# test.net
KiCad netlist of a schematic drawn in EAGLE
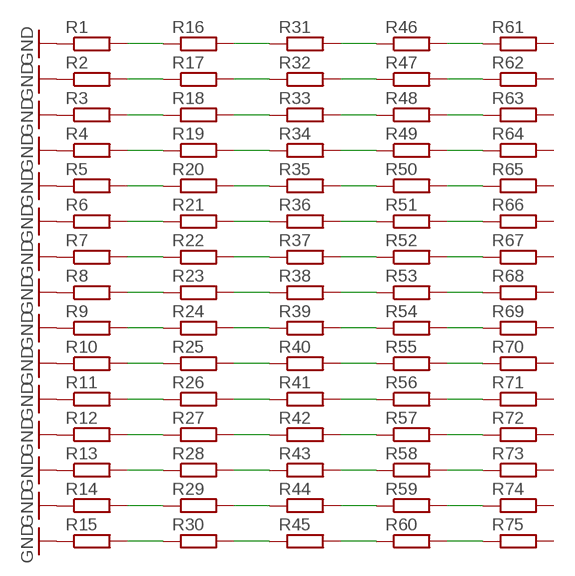
[diagram p0: schematic, sheet 1]

(export (version "E")
  (design (tool "Eeschema 10.0.6"))
  (components
    (comp (ref "R1")
      (value "R-EU_R1206")
      (footprint "eagle-import:R1206")
      (libsource (lib "eagle-import") (part "R-EU_R1206"))
    )
    (comp (ref "R2")
      (value "R-EU_R1206")
      (footprint "eagle-import:R1206")
      (libsource (lib "eagle-import") (part "R-EU_R1206"))
    )
    (comp (ref "R3")
      (value "R-EU_R1206")
      (footprint "eagle-import:R1206")
      (libsource (lib "eagle-import") (part "R-EU_R1206"))
    )
    (comp (ref "R4")
      (value "R-EU_R1206")
      (footprint "eagle-import:R1206")
      (libsource (lib "eagle-import") (part "R-EU_R1206"))
    )
    (comp (ref "R5")
      (value "R-EU_R1206")
      (footprint "eagle-import:R1206")
      (libsource (lib "eagle-import") (part "R-EU_R1206"))
    )
    (comp (ref "R6")
      (value "R-EU_R1206")
      (footprint "eagle-import:R1206")
      (libsource (lib "eagle-import") (part "R-EU_R1206"))
    )
    (comp (ref "R7")
      (value "R-EU_R1206")
      (footprint "eagle-import:R1206")
      (libsource (lib "eagle-import") (part "R-EU_R1206"))
    )
    (comp (ref "R8")
      (value "R-EU_R1206")
      (footprint "eagle-import:R1206")
      (libsource (lib "eagle-import") (part "R-EU_R1206"))
    )
    (comp (ref "R9")
      (value "R-EU_R1206")
      (footprint "eagle-import:R1206")
      (libsource (lib "eagle-import") (part "R-EU_R1206"))
    )
    (comp (ref "R10")
      (value "R-EU_R1206")
      (footprint "eagle-import:R1206")
      (libsource (lib "eagle-import") (part "R-EU_R1206"))
    )
    (comp (ref "R11")
      (value "R-EU_R1206")
      (footprint "eagle-import:R1206")
      (libsource (lib "eagle-import") (part "R-EU_R1206"))
    )
    (comp (ref "R12")
      (value "R-EU_R1206")
      (footprint "eagle-import:R1206")
      (libsource (lib "eagle-import") (part "R-EU_R1206"))
    )
    (comp (ref "R13")
      (value "R-EU_R1206")
      (footprint "eagle-import:R1206")
      (libsource (lib "eagle-import") (part "R-EU_R1206"))
    )
    (comp (ref "R14")
      (value "R-EU_R1206")
      (footprint "eagle-import:R1206")
      (libsource (lib "eagle-import") (part "R-EU_R1206"))
    )
    (comp (ref "R15")
      (value "R-EU_R1206")
      (footprint "eagle-import:R1206")
      (libsource (lib "eagle-import") (part "R-EU_R1206"))
    )
    (comp (ref "R16")
      (value "R-EU_R1206")
      (footprint "eagle-import:R1206")
      (libsource (lib "eagle-import") (part "R-EU_R1206"))
    )
    (comp (ref "R17")
      (value "R-EU_R1206")
      (footprint "eagle-import:R1206")
      (libsource (lib "eagle-import") (part "R-EU_R1206"))
    )
    (comp (ref "R18")
      (value "R-EU_R1206")
      (footprint "eagle-import:R1206")
      (libsource (lib "eagle-import") (part "R-EU_R1206"))
    )
    (comp (ref "R19")
      (value "R-EU_R1206")
      (footprint "eagle-import:R1206")
      (libsource (lib "eagle-import") (part "R-EU_R1206"))
    )
    (comp (ref "R20")
      (value "R-EU_R1206")
      (footprint "eagle-import:R1206")
      (libsource (lib "eagle-import") (part "R-EU_R1206"))
    )
    (comp (ref "R21")
      (value "R-EU_R1206")
      (footprint "eagle-import:R1206")
      (libsource (lib "eagle-import") (part "R-EU_R1206"))
    )
    (comp (ref "R22")
      (value "R-EU_R1206")
      (footprint "eagle-import:R1206")
      (libsource (lib "eagle-import") (part "R-EU_R1206"))
    )
    (comp (ref "R23")
      (value "R-EU_R1206")
      (footprint "eagle-import:R1206")
      (libsource (lib "eagle-import") (part "R-EU_R1206"))
    )
    (comp (ref "R24")
      (value "R-EU_R1206")
      (footprint "eagle-import:R1206")
      (libsource (lib "eagle-import") (part "R-EU_R1206"))
    )
    (comp (ref "R25")
      (value "R-EU_R1206")
      (footprint "eagle-import:R1206")
      (libsource (lib "eagle-import") (part "R-EU_R1206"))
    )
    (comp (ref "R26")
      (value "R-EU_R1206")
      (footprint "eagle-import:R1206")
      (libsource (lib "eagle-import") (part "R-EU_R1206"))
    )
    (comp (ref "R27")
      (value "R-EU_R1206")
      (footprint "eagle-import:R1206")
      (libsource (lib "eagle-import") (part "R-EU_R1206"))
    )
    (comp (ref "R28")
      (value "R-EU_R1206")
      (footprint "eagle-import:R1206")
      (libsource (lib "eagle-import") (part "R-EU_R1206"))
    )
    (comp (ref "R29")
      (value "R-EU_R1206")
      (footprint "eagle-import:R1206")
      (libsource (lib "eagle-import") (part "R-EU_R1206"))
    )
    (comp (ref "R30")
      (value "R-EU_R1206")
      (footprint "eagle-import:R1206")
      (libsource (lib "eagle-import") (part "R-EU_R1206"))
    )
    (comp (ref "R31")
      (value "R-EU_R1206")
      (footprint "eagle-import:R1206")
      (libsource (lib "eagle-import") (part "R-EU_R1206"))
    )
    (comp (ref "R32")
      (value "R-EU_R1206")
      (footprint "eagle-import:R1206")
      (libsource (lib "eagle-import") (part "R-EU_R1206"))
    )
    (comp (ref "R33")
      (value "R-EU_R1206")
      (footprint "eagle-import:R1206")
      (libsource (lib "eagle-import") (part "R-EU_R1206"))
    )
    (comp (ref "R34")
      (value "R-EU_R1206")
      (footprint "eagle-import:R1206")
      (libsource (lib "eagle-import") (part "R-EU_R1206"))
    )
    (comp (ref "R35")
      (value "R-EU_R1206")
      (footprint "eagle-import:R1206")
      (libsource (lib "eagle-import") (part "R-EU_R1206"))
    )
    (comp (ref "R36")
      (value "R-EU_R1206")
      (footprint "eagle-import:R1206")
      (libsource (lib "eagle-import") (part "R-EU_R1206"))
    )
    (comp (ref "R37")
      (value "R-EU_R1206")
      (footprint "eagle-import:R1206")
      (libsource (lib "eagle-import") (part "R-EU_R1206"))
    )
    (comp (ref "R38")
      (value "R-EU_R1206")
      (footprint "eagle-import:R1206")
      (libsource (lib "eagle-import") (part "R-EU_R1206"))
    )
    (comp (ref "R39")
      (value "R-EU_R1206")
      (footprint "eagle-import:R1206")
      (libsource (lib "eagle-import") (part "R-EU_R1206"))
    )
    (comp (ref "R40")
      (value "R-EU_R1206")
      (footprint "eagle-import:R1206")
      (libsource (lib "eagle-import") (part "R-EU_R1206"))
    )
    (comp (ref "R41")
      (value "R-EU_R1206")
      (footprint "eagle-import:R1206")
      (libsource (lib "eagle-import") (part "R-EU_R1206"))
    )
    (comp (ref "R42")
      (value "R-EU_R1206")
      (footprint "eagle-import:R1206")
      (libsource (lib "eagle-import") (part "R-EU_R1206"))
    )
    (comp (ref "R43")
      (value "R-EU_R1206")
      (footprint "eagle-import:R1206")
      (libsource (lib "eagle-import") (part "R-EU_R1206"))
    )
    (comp (ref "R44")
      (value "R-EU_R1206")
      (footprint "eagle-import:R1206")
      (libsource (lib "eagle-import") (part "R-EU_R1206"))
    )
    (comp (ref "R45")
      (value "R-EU_R1206")
      (footprint "eagle-import:R1206")
      (libsource (lib "eagle-import") (part "R-EU_R1206"))
    )
    (comp (ref "R46")
      (value "R-EU_R1206")
      (footprint "eagle-import:R1206")
      (libsource (lib "eagle-import") (part "R-EU_R1206"))
    )
    (comp (ref "R47")
      (value "R-EU_R1206")
      (footprint "eagle-import:R1206")
      (libsource (lib "eagle-import") (part "R-EU_R1206"))
    )
    (comp (ref "R48")
      (value "R-EU_R1206")
      (footprint "eagle-import:R1206")
      (libsource (lib "eagle-import") (part "R-EU_R1206"))
    )
    (comp (ref "R49")
      (value "R-EU_R1206")
      (footprint "eagle-import:R1206")
      (libsource (lib "eagle-import") (part "R-EU_R1206"))
    )
    (comp (ref "R50")
      (value "R-EU_R1206")
      (footprint "eagle-import:R1206")
      (libsource (lib "eagle-import") (part "R-EU_R1206"))
    )
    (comp (ref "R51")
      (value "R-EU_R1206")
      (footprint "eagle-import:R1206")
      (libsource (lib "eagle-import") (part "R-EU_R1206"))
    )
    (comp (ref "R52")
      (value "R-EU_R1206")
      (footprint "eagle-import:R1206")
      (libsource (lib "eagle-import") (part "R-EU_R1206"))
    )
    (comp (ref "R53")
      (value "R-EU_R1206")
      (footprint "eagle-import:R1206")
      (libsource (lib "eagle-import") (part "R-EU_R1206"))
    )
    (comp (ref "R54")
      (value "R-EU_R1206")
      (footprint "eagle-import:R1206")
      (libsource (lib "eagle-import") (part "R-EU_R1206"))
    )
    (comp (ref "R55")
      (value "R-EU_R1206")
      (footprint "eagle-import:R1206")
      (libsource (lib "eagle-import") (part "R-EU_R1206"))
    )
    (comp (ref "R56")
      (value "R-EU_R1206")
      (footprint "eagle-import:R1206")
      (libsource (lib "eagle-import") (part "R-EU_R1206"))
    )
    (comp (ref "R57")
      (value "R-EU_R1206")
      (footprint "eagle-import:R1206")
      (libsource (lib "eagle-import") (part "R-EU_R1206"))
    )
    (comp (ref "R58")
      (value "R-EU_R1206")
      (footprint "eagle-import:R1206")
      (libsource (lib "eagle-import") (part "R-EU_R1206"))
    )
    (comp (ref "R59")
      (value "R-EU_R1206")
      (footprint "eagle-import:R1206")
      (libsource (lib "eagle-import") (part "R-EU_R1206"))
    )
    (comp (ref "R60")
      (value "R-EU_R1206")
      (footprint "eagle-import:R1206")
      (libsource (lib "eagle-import") (part "R-EU_R1206"))
    )
    (comp (ref "R61")
      (value "R-EU_R1206")
      (footprint "eagle-import:R1206")
      (libsource (lib "eagle-import") (part "R-EU_R1206"))
    )
    (comp (ref "R62")
      (value "R-EU_R1206")
      (footprint "eagle-import:R1206")
      (libsource (lib "eagle-import") (part "R-EU_R1206"))
    )
    (comp (ref "R63")
      (value "R-EU_R1206")
      (footprint "eagle-import:R1206")
      (libsource (lib "eagle-import") (part "R-EU_R1206"))
    )
    (comp (ref "R64")
      (value "R-EU_R1206")
      (footprint "eagle-import:R1206")
      (libsource (lib "eagle-import") (part "R-EU_R1206"))
    )
    (comp (ref "R65")
      (value "R-EU_R1206")
      (footprint "eagle-import:R1206")
      (libsource (lib "eagle-import") (part "R-EU_R1206"))
    )
    (comp (ref "R66")
      (value "R-EU_R1206")
      (footprint "eagle-import:R1206")
      (libsource (lib "eagle-import") (part "R-EU_R1206"))
    )
    (comp (ref "R67")
      (value "R-EU_R1206")
      (footprint "eagle-import:R1206")
      (libsource (lib "eagle-import") (part "R-EU_R1206"))
    )
    (comp (ref "R68")
      (value "R-EU_R1206")
      (footprint "eagle-import:R1206")
      (libsource (lib "eagle-import") (part "R-EU_R1206"))
    )
    (comp (ref "R69")
      (value "R-EU_R1206")
      (footprint "eagle-import:R1206")
      (libsource (lib "eagle-import") (part "R-EU_R1206"))
    )
    (comp (ref "R70")
      (value "R-EU_R1206")
      (footprint "eagle-import:R1206")
      (libsource (lib "eagle-import") (part "R-EU_R1206"))
    )
    (comp (ref "R71")
      (value "R-EU_R1206")
      (footprint "eagle-import:R1206")
      (libsource (lib "eagle-import") (part "R-EU_R1206"))
    )
    (comp (ref "R72")
      (value "R-EU_R1206")
      (footprint "eagle-import:R1206")
      (libsource (lib "eagle-import") (part "R-EU_R1206"))
    )
    (comp (ref "R73")
      (value "R-EU_R1206")
      (footprint "eagle-import:R1206")
      (libsource (lib "eagle-import") (part "R-EU_R1206"))
    )
    (comp (ref "R74")
      (value "R-EU_R1206")
      (footprint "eagle-import:R1206")
      (libsource (lib "eagle-import") (part "R-EU_R1206"))
    )
    (comp (ref "R75")
      (value "R-EU_R1206")
      (footprint "eagle-import:R1206")
      (libsource (lib "eagle-import") (part "R-EU_R1206"))
    )
  )
  (nets
    (net (code "1") (name "GND") (class "Default")
      (node (ref "R1") (pin "1") (pinfunction "1_1") (pintype "passive"))
      (node (ref "R10") (pin "1") (pinfunction "1_1") (pintype "passive"))
      (node (ref "R11") (pin "1") (pinfunction "1_1") (pintype "passive"))
      (node (ref "R12") (pin "1") (pinfunction "1_1") (pintype "passive"))
      (node (ref "R13") (pin "1") (pinfunction "1_1") (pintype "passive"))
      (node (ref "R14") (pin "1") (pinfunction "1_1") (pintype "passive"))
      (node (ref "R15") (pin "1") (pinfunction "1_1") (pintype "passive"))
      (node (ref "R2") (pin "1") (pinfunction "1_1") (pintype "passive"))
      (node (ref "R3") (pin "1") (pinfunction "1_1") (pintype "passive"))
      (node (ref "R4") (pin "1") (pinfunction "1_1") (pintype "passive"))
      (node (ref "R5") (pin "1") (pinfunction "1_1") (pintype "passive"))
      (node (ref "R6") (pin "1") (pinfunction "1_1") (pintype "passive"))
      (node (ref "R7") (pin "1") (pinfunction "1_1") (pintype "passive"))
      (node (ref "R8") (pin "1") (pinfunction "1_1") (pintype "passive"))
      (node (ref "R9") (pin "1") (pinfunction "1_1") (pintype "passive"))
    )
    (net (code "2") (name "Net-(R1-Pad2)") (class "Default")
      (node (ref "R1") (pin "2") (pinfunction "2_2") (pintype "passive"))
      (node (ref "R16") (pin "1") (pinfunction "1_1") (pintype "passive"))
    )
    (net (code "3") (name "Net-(R10-Pad2)") (class "Default")
      (node (ref "R10") (pin "2") (pinfunction "2_2") (pintype "passive"))
      (node (ref "R25") (pin "1") (pinfunction "1_1") (pintype "passive"))
    )
    (net (code "4") (name "Net-(R11-Pad2)") (class "Default")
      (node (ref "R11") (pin "2") (pinfunction "2_2") (pintype "passive"))
      (node (ref "R26") (pin "1") (pinfunction "1_1") (pintype "passive"))
    )
    (net (code "5") (name "Net-(R12-Pad2)") (class "Default")
      (node (ref "R12") (pin "2") (pinfunction "2_2") (pintype "passive"))
      (node (ref "R27") (pin "1") (pinfunction "1_1") (pintype "passive"))
    )
    (net (code "6") (name "Net-(R13-Pad2)") (class "Default")
      (node (ref "R13") (pin "2") (pinfunction "2_2") (pintype "passive"))
      (node (ref "R28") (pin "1") (pinfunction "1_1") (pintype "passive"))
    )
    (net (code "7") (name "Net-(R14-Pad2)") (class "Default")
      (node (ref "R14") (pin "2") (pinfunction "2_2") (pintype "passive"))
      (node (ref "R29") (pin "1") (pinfunction "1_1") (pintype "passive"))
    )
    (net (code "8") (name "Net-(R15-Pad2)") (class "Default")
      (node (ref "R15") (pin "2") (pinfunction "2_2") (pintype "passive"))
      (node (ref "R30") (pin "1") (pinfunction "1_1") (pintype "passive"))
    )
    (net (code "9") (name "Net-(R16-Pad2)") (class "Default")
      (node (ref "R16") (pin "2") (pinfunction "2_2") (pintype "passive"))
      (node (ref "R31") (pin "1") (pinfunction "1_1") (pintype "passive"))
    )
    (net (code "10") (name "Net-(R17-Pad1)") (class "Default")
      (node (ref "R17") (pin "1") (pinfunction "1_1") (pintype "passive"))
      (node (ref "R2") (pin "2") (pinfunction "2_2") (pintype "passive"))
    )
    (net (code "11") (name "Net-(R17-Pad2)") (class "Default")
      (node (ref "R17") (pin "2") (pinfunction "2_2") (pintype "passive"))
      (node (ref "R32") (pin "1") (pinfunction "1_1") (pintype "passive"))
    )
    (net (code "12") (name "Net-(R18-Pad1)") (class "Default")
      (node (ref "R18") (pin "1") (pinfunction "1_1") (pintype "passive"))
      (node (ref "R3") (pin "2") (pinfunction "2_2") (pintype "passive"))
    )
    (net (code "13") (name "Net-(R18-Pad2)") (class "Default")
      (node (ref "R18") (pin "2") (pinfunction "2_2") (pintype "passive"))
      (node (ref "R33") (pin "1") (pinfunction "1_1") (pintype "passive"))
    )
    (net (code "14") (name "Net-(R19-Pad1)") (class "Default")
      (node (ref "R19") (pin "1") (pinfunction "1_1") (pintype "passive"))
      (node (ref "R4") (pin "2") (pinfunction "2_2") (pintype "passive"))
    )
    (net (code "15") (name "Net-(R19-Pad2)") (class "Default")
      (node (ref "R19") (pin "2") (pinfunction "2_2") (pintype "passive"))
      (node (ref "R34") (pin "1") (pinfunction "1_1") (pintype "passive"))
    )
    (net (code "16") (name "Net-(R20-Pad1)") (class "Default")
      (node (ref "R20") (pin "1") (pinfunction "1_1") (pintype "passive"))
      (node (ref "R5") (pin "2") (pinfunction "2_2") (pintype "passive"))
    )
    (net (code "17") (name "Net-(R20-Pad2)") (class "Default")
      (node (ref "R20") (pin "2") (pinfunction "2_2") (pintype "passive"))
      (node (ref "R35") (pin "1") (pinfunction "1_1") (pintype "passive"))
    )
    (net (code "18") (name "Net-(R21-Pad1)") (class "Default")
      (node (ref "R21") (pin "1") (pinfunction "1_1") (pintype "passive"))
      (node (ref "R6") (pin "2") (pinfunction "2_2") (pintype "passive"))
    )
    (net (code "19") (name "Net-(R21-Pad2)") (class "Default")
      (node (ref "R21") (pin "2") (pinfunction "2_2") (pintype "passive"))
      (node (ref "R36") (pin "1") (pinfunction "1_1") (pintype "passive"))
    )
    (net (code "20") (name "Net-(R22-Pad1)") (class "Default")
      (node (ref "R22") (pin "1") (pinfunction "1_1") (pintype "passive"))
      (node (ref "R7") (pin "2") (pinfunction "2_2") (pintype "passive"))
    )
    (net (code "21") (name "Net-(R22-Pad2)") (class "Default")
      (node (ref "R22") (pin "2") (pinfunction "2_2") (pintype "passive"))
      (node (ref "R37") (pin "1") (pinfunction "1_1") (pintype "passive"))
    )
    (net (code "22") (name "Net-(R23-Pad1)") (class "Default")
      (node (ref "R23") (pin "1") (pinfunction "1_1") (pintype "passive"))
      (node (ref "R8") (pin "2") (pinfunction "2_2") (pintype "passive"))
    )
    (net (code "23") (name "Net-(R23-Pad2)") (class "Default")
      (node (ref "R23") (pin "2") (pinfunction "2_2") (pintype "passive"))
      (node (ref "R38") (pin "1") (pinfunction "1_1") (pintype "passive"))
    )
    (net (code "24") (name "Net-(R24-Pad1)") (class "Default")
      (node (ref "R24") (pin "1") (pinfunction "1_1") (pintype "passive"))
      (node (ref "R9") (pin "2") (pinfunction "2_2") (pintype "passive"))
    )
    (net (code "25") (name "Net-(R24-Pad2)") (class "Default")
      (node (ref "R24") (pin "2") (pinfunction "2_2") (pintype "passive"))
      (node (ref "R39") (pin "1") (pinfunction "1_1") (pintype "passive"))
    )
    (net (code "26") (name "Net-(R25-Pad2)") (class "Default")
      (node (ref "R25") (pin "2") (pinfunction "2_2") (pintype "passive"))
      (node (ref "R40") (pin "1") (pinfunction "1_1") (pintype "passive"))
    )
    (net (code "27") (name "Net-(R26-Pad2)") (class "Default")
      (node (ref "R26") (pin "2") (pinfunction "2_2") (pintype "passive"))
      (node (ref "R41") (pin "1") (pinfunction "1_1") (pintype "passive"))
    )
    (net (code "28") (name "Net-(R27-Pad2)") (class "Default")
      (node (ref "R27") (pin "2") (pinfunction "2_2") (pintype "passive"))
      (node (ref "R42") (pin "1") (pinfunction "1_1") (pintype "passive"))
    )
    (net (code "29") (name "Net-(R28-Pad2)") (class "Default")
      (node (ref "R28") (pin "2") (pinfunction "2_2") (pintype "passive"))
      (node (ref "R43") (pin "1") (pinfunction "1_1") (pintype "passive"))
    )
    (net (code "30") (name "Net-(R29-Pad2)") (class "Default")
      (node (ref "R29") (pin "2") (pinfunction "2_2") (pintype "passive"))
      (node (ref "R44") (pin "1") (pinfunction "1_1") (pintype "passive"))
    )
    (net (code "31") (name "Net-(R30-Pad2)") (class "Default")
      (node (ref "R30") (pin "2") (pinfunction "2_2") (pintype "passive"))
      (node (ref "R45") (pin "1") (pinfunction "1_1") (pintype "passive"))
    )
    (net (code "32") (name "Net-(R31-Pad2)") (class "Default")
      (node (ref "R31") (pin "2") (pinfunction "2_2") (pintype "passive"))
      (node (ref "R46") (pin "1") (pinfunction "1_1") (pintype "passive"))
    )
    (net (code "33") (name "Net-(R32-Pad2)") (class "Default")
      (node (ref "R32") (pin "2") (pinfunction "2_2") (pintype "passive"))
      (node (ref "R47") (pin "1") (pinfunction "1_1") (pintype "passive"))
    )
    (net (code "34") (name "Net-(R33-Pad2)") (class "Default")
      (node (ref "R33") (pin "2") (pinfunction "2_2") (pintype "passive"))
      (node (ref "R48") (pin "1") (pinfunction "1_1") (pintype "passive"))
    )
    (net (code "35") (name "Net-(R34-Pad2)") (class "Default")
      (node (ref "R34") (pin "2") (pinfunction "2_2") (pintype "passive"))
      (node (ref "R49") (pin "1") (pinfunction "1_1") (pintype "passive"))
    )
    (net (code "36") (name "Net-(R35-Pad2)") (class "Default")
      (node (ref "R35") (pin "2") (pinfunction "2_2") (pintype "passive"))
      (node (ref "R50") (pin "1") (pinfunction "1_1") (pintype "passive"))
    )
    (net (code "37") (name "Net-(R36-Pad2)") (class "Default")
      (node (ref "R36") (pin "2") (pinfunction "2_2") (pintype "passive"))
      (node (ref "R51") (pin "1") (pinfunction "1_1") (pintype "passive"))
    )
    (net (code "38") (name "Net-(R37-Pad2)") (class "Default")
      (node (ref "R37") (pin "2") (pinfunction "2_2") (pintype "passive"))
      (node (ref "R52") (pin "1") (pinfunction "1_1") (pintype "passive"))
    )
    (net (code "39") (name "Net-(R38-Pad2)") (class "Default")
      (node (ref "R38") (pin "2") (pinfunction "2_2") (pintype "passive"))
      (node (ref "R53") (pin "1") (pinfunction "1_1") (pintype "passive"))
    )
    (net (code "40") (name "Net-(R39-Pad2)") (class "Default")
      (node (ref "R39") (pin "2") (pinfunction "2_2") (pintype "passive"))
      (node (ref "R54") (pin "1") (pinfunction "1_1") (pintype "passive"))
    )
    (net (code "41") (name "Net-(R40-Pad2)") (class "Default")
      (node (ref "R40") (pin "2") (pinfunction "2_2") (pintype "passive"))
      (node (ref "R55") (pin "1") (pinfunction "1_1") (pintype "passive"))
    )
    (net (code "42") (name "Net-(R41-Pad2)") (class "Default")
      (node (ref "R41") (pin "2") (pinfunction "2_2") (pintype "passive"))
      (node (ref "R56") (pin "1") (pinfunction "1_1") (pintype "passive"))
    )
    (net (code "43") (name "Net-(R42-Pad2)") (class "Default")
      (node (ref "R42") (pin "2") (pinfunction "2_2") (pintype "passive"))
      (node (ref "R57") (pin "1") (pinfunction "1_1") (pintype "passive"))
    )
    (net (code "44") (name "Net-(R43-Pad2)") (class "Default")
      (node (ref "R43") (pin "2") (pinfunction "2_2") (pintype "passive"))
      (node (ref "R58") (pin "1") (pinfunction "1_1") (pintype "passive"))
    )
    (net (code "45") (name "Net-(R44-Pad2)") (class "Default")
      (node (ref "R44") (pin "2") (pinfunction "2_2") (pintype "passive"))
      (node (ref "R59") (pin "1") (pinfunction "1_1") (pintype "passive"))
    )
    (net (code "46") (name "Net-(R45-Pad2)") (class "Default")
      (node (ref "R45") (pin "2") (pinfunction "2_2") (pintype "passive"))
      (node (ref "R60") (pin "1") (pinfunction "1_1") (pintype "passive"))
    )
    (net (code "47") (name "Net-(R46-Pad2)") (class "Default")
      (node (ref "R46") (pin "2") (pinfunction "2_2") (pintype "passive"))
      (node (ref "R61") (pin "1") (pinfunction "1_1") (pintype "passive"))
    )
    (net (code "48") (name "Net-(R47-Pad2)") (class "Default")
      (node (ref "R47") (pin "2") (pinfunction "2_2") (pintype "passive"))
      (node (ref "R62") (pin "1") (pinfunction "1_1") (pintype "passive"))
    )
    (net (code "49") (name "Net-(R48-Pad2)") (class "Default")
      (node (ref "R48") (pin "2") (pinfunction "2_2") (pintype "passive"))
      (node (ref "R63") (pin "1") (pinfunction "1_1") (pintype "passive"))
    )
    (net (code "50") (name "Net-(R49-Pad2)") (class "Default")
      (node (ref "R49") (pin "2") (pinfunction "2_2") (pintype "passive"))
      (node (ref "R64") (pin "1") (pinfunction "1_1") (pintype "passive"))
    )
    (net (code "51") (name "Net-(R50-Pad2)") (class "Default")
      (node (ref "R50") (pin "2") (pinfunction "2_2") (pintype "passive"))
      (node (ref "R65") (pin "1") (pinfunction "1_1") (pintype "passive"))
    )
    (net (code "52") (name "Net-(R51-Pad2)") (class "Default")
      (node (ref "R51") (pin "2") (pinfunction "2_2") (pintype "passive"))
      (node (ref "R66") (pin "1") (pinfunction "1_1") (pintype "passive"))
    )
    (net (code "53") (name "Net-(R52-Pad2)") (class "Default")
      (node (ref "R52") (pin "2") (pinfunction "2_2") (pintype "passive"))
      (node (ref "R67") (pin "1") (pinfunction "1_1") (pintype "passive"))
    )
    (net (code "54") (name "Net-(R53-Pad2)") (class "Default")
      (node (ref "R53") (pin "2") (pinfunction "2_2") (pintype "passive"))
      (node (ref "R68") (pin "1") (pinfunction "1_1") (pintype "passive"))
    )
    (net (code "55") (name "Net-(R54-Pad2)") (class "Default")
      (node (ref "R54") (pin "2") (pinfunction "2_2") (pintype "passive"))
      (node (ref "R69") (pin "1") (pinfunction "1_1") (pintype "passive"))
    )
    (net (code "56") (name "Net-(R55-Pad2)") (class "Default")
      (node (ref "R55") (pin "2") (pinfunction "2_2") (pintype "passive"))
      (node (ref "R70") (pin "1") (pinfunction "1_1") (pintype "passive"))
    )
    (net (code "57") (name "Net-(R56-Pad2)") (class "Default")
      (node (ref "R56") (pin "2") (pinfunction "2_2") (pintype "passive"))
      (node (ref "R71") (pin "1") (pinfunction "1_1") (pintype "passive"))
    )
    (net (code "58") (name "Net-(R57-Pad2)") (class "Default")
      (node (ref "R57") (pin "2") (pinfunction "2_2") (pintype "passive"))
      (node (ref "R72") (pin "1") (pinfunction "1_1") (pintype "passive"))
    )
    (net (code "59") (name "Net-(R58-Pad2)") (class "Default")
      (node (ref "R58") (pin "2") (pinfunction "2_2") (pintype "passive"))
      (node (ref "R73") (pin "1") (pinfunction "1_1") (pintype "passive"))
    )
    (net (code "60") (name "Net-(R59-Pad2)") (class "Default")
      (node (ref "R59") (pin "2") (pinfunction "2_2") (pintype "passive"))
      (node (ref "R74") (pin "1") (pinfunction "1_1") (pintype "passive"))
    )
    (net (code "61") (name "Net-(R60-Pad2)") (class "Default")
      (node (ref "R60") (pin "2") (pinfunction "2_2") (pintype "passive"))
      (node (ref "R75") (pin "1") (pinfunction "1_1") (pintype "passive"))
    )
    (net (code "62") (name "unconnected-(R61-Pad2)") (class "Default")
      (node (ref "R61") (pin "2") (pinfunction "2_2") (pintype "passive"))
    )
    (net (code "63") (name "unconnected-(R62-Pad2)") (class "Default")
      (node (ref "R62") (pin "2") (pinfunction "2_2") (pintype "passive"))
    )
    (net (code "64") (name "unconnected-(R63-Pad2)") (class "Default")
      (node (ref "R63") (pin "2") (pinfunction "2_2") (pintype "passive"))
    )
    (net (code "65") (name "unconnected-(R64-Pad2)") (class "Default")
      (node (ref "R64") (pin "2") (pinfunction "2_2") (pintype "passive"))
    )
    (net (code "66") (name "unconnected-(R65-Pad2)") (class "Default")
      (node (ref "R65") (pin "2") (pinfunction "2_2") (pintype "passive"))
    )
    (net (code "67") (name "unconnected-(R66-Pad2)") (class "Default")
      (node (ref "R66") (pin "2") (pinfunction "2_2") (pintype "passive"))
    )
    (net (code "68") (name "unconnected-(R67-Pad2)") (class "Default")
      (node (ref "R67") (pin "2") (pinfunction "2_2") (pintype "passive"))
    )
    (net (code "69") (name "unconnected-(R68-Pad2)") (class "Default")
      (node (ref "R68") (pin "2") (pinfunction "2_2") (pintype "passive"))
    )
    (net (code "70") (name "unconnected-(R69-Pad2)") (class "Default")
      (node (ref "R69") (pin "2") (pinfunction "2_2") (pintype "passive"))
    )
    (net (code "71") (name "unconnected-(R70-Pad2)") (class "Default")
      (node (ref "R70") (pin "2") (pinfunction "2_2") (pintype "passive"))
    )
    (net (code "72") (name "unconnected-(R71-Pad2)") (class "Default")
      (node (ref "R71") (pin "2") (pinfunction "2_2") (pintype "passive"))
    )
    (net (code "73") (name "unconnected-(R72-Pad2)") (class "Default")
      (node (ref "R72") (pin "2") (pinfunction "2_2") (pintype "passive"))
    )
    (net (code "74") (name "unconnected-(R73-Pad2)") (class "Default")
      (node (ref "R73") (pin "2") (pinfunction "2_2") (pintype "passive"))
    )
    (net (code "75") (name "unconnected-(R74-Pad2)") (class "Default")
      (node (ref "R74") (pin "2") (pinfunction "2_2") (pintype "passive"))
    )
    (net (code "76") (name "unconnected-(R75-Pad2)") (class "Default")
      (node (ref "R75") (pin "2") (pinfunction "2_2") (pintype "passive"))
    )
  )
)
